# STM32Fx.net
KiCad netlist of a schematic drawn in Altium Designer
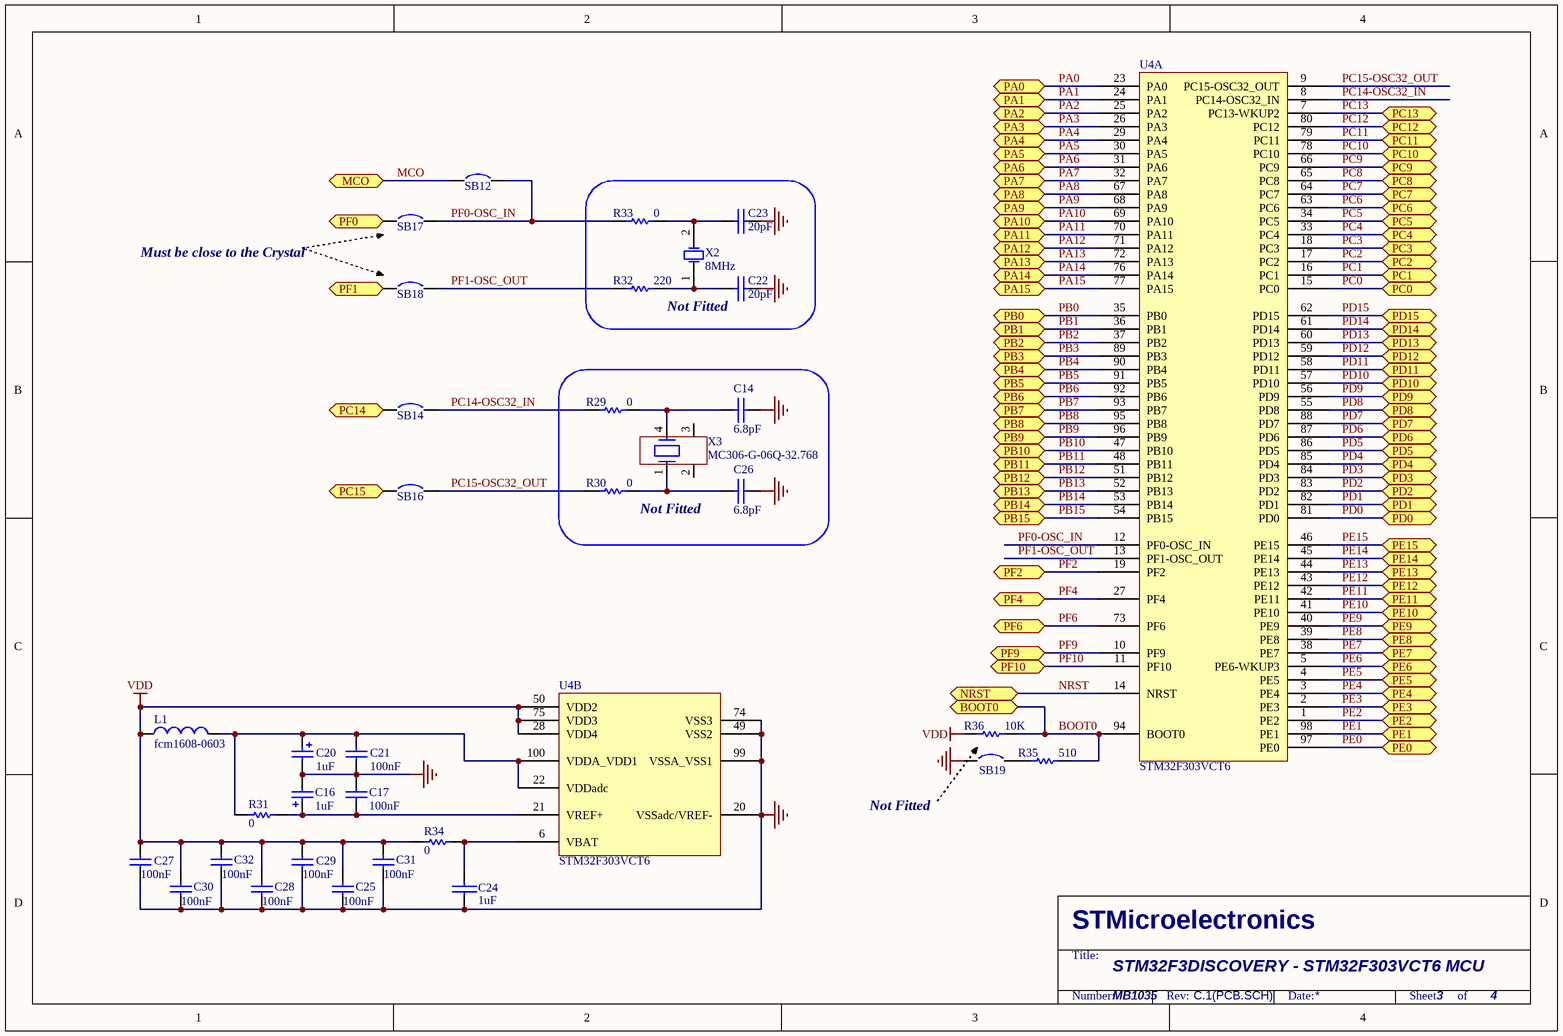
[diagram p0: STM32Fx.SchDoc]

(export (version "E")
  (design (tool "Eeschema 10.0.6"))
  (components
    (comp (ref "C14")
      (value "6.8pF")
      (footprint "0603C")
      (description "Capacitor")
      (libsource (lib "") (part "CAP_1"))
    )
    (comp (ref "C16")
      (value "1uF")
      (footprint "CASE-AA")
      (description "Polarized Capacitor (Radial)")
      (fields (field (name "PUBLISHER") "Altium Limited"))
      (libsource (lib "Miscellaneous Devices") (part "Cap Pol1"))
    )
    (comp (ref "C17")
      (value "100nF")
      (footprint "0603C")
      (description "Capacitor")
      (fields (field (name "PUBLISHER") "Altium Limited"))
      (libsource (lib "MB915_1") (part "Cap"))
    )
    (comp (ref "C20")
      (value "1uF")
      (footprint "CASE-AA")
      (description "Polarized Capacitor (Radial)")
      (fields (field (name "PUBLISHER") "Altium Limited"))
      (libsource (lib "Miscellaneous Devices") (part "Cap Pol1"))
    )
    (comp (ref "C21")
      (value "100nF")
      (footprint "0603C")
      (description "Capacitor")
      (fields (field (name "PUBLISHER") "Altium Limited"))
      (libsource (lib "MB915_1") (part "Cap"))
    )
    (comp (ref "C22")
      (value "20pF")
      (footprint "0603C")
      (description "Capacitor")
      (libsource (lib "*") (part "CAP"))
    )
    (comp (ref "C23")
      (value "20pF")
      (footprint "0603C")
      (description "Capacitor")
      (libsource (lib "*") (part "CAP"))
    )
    (comp (ref "C24")
      (value "1uF")
      (footprint "0603C")
      (description "Capacitor")
      (libsource (lib "*") (part "CAP"))
    )
    (comp (ref "C25")
      (value "100nF")
      (footprint "0603C")
      (description "Capacitor")
      (fields (field (name "PUBLISHER") "Altium Limited"))
      (libsource (lib "MB915_1") (part "Cap"))
    )
    (comp (ref "C26")
      (value "6.8pF")
      (footprint "0603C")
      (description "Capacitor")
      (libsource (lib "") (part "CAP_1"))
    )
    (comp (ref "C27")
      (value "100nF")
      (footprint "0603C")
      (description "Capacitor")
      (fields (field (name "PUBLISHER") "Altium Limited"))
      (libsource (lib "MB915_1") (part "Cap"))
    )
    (comp (ref "C28")
      (value "100nF")
      (footprint "0603C")
      (description "Capacitor")
      (fields (field (name "PUBLISHER") "Altium Limited"))
      (libsource (lib "MB915_1") (part "Cap"))
    )
    (comp (ref "C29")
      (value "100nF")
      (footprint "0603C")
      (description "Capacitor")
      (fields (field (name "PUBLISHER") "Altium Limited"))
      (libsource (lib "MB915_1") (part "Cap"))
    )
    (comp (ref "C30")
      (value "100nF")
      (footprint "0603C")
      (description "Capacitor")
      (fields (field (name "PUBLISHER") "Altium Limited"))
      (libsource (lib "MB915_1") (part "Cap"))
    )
    (comp (ref "C31")
      (value "100nF")
      (footprint "0603C")
      (description "Capacitor")
      (fields (field (name "PUBLISHER") "Altium Limited"))
      (libsource (lib "MB915_1") (part "Cap"))
    )
    (comp (ref "C32")
      (value "100nF")
      (footprint "0603C")
      (description "Capacitor")
      (fields (field (name "PUBLISHER") "Altium Limited"))
      (libsource (lib "MB915_1") (part "Cap"))
    )
    (comp (ref "L1")
      (value "fcm1608-0603")
      (footprint "0603L")
      (description "Inductor")
      (fields (field (name "PUBLISHER") "Altium Limited"))
      (libsource (lib "Miscellaneous Devices") (part "Inductor"))
    )
    (comp (ref "R29")
      (value "0")
      (footprint "0402R")
      (description "Resistor")
      (fields (field (name "PUBLISHER") "Altium Limited"))
      (libsource (lib "MB915_1") (part "res1"))
    )
    (comp (ref "R30")
      (value "0")
      (footprint "0402R")
      (description "Resistor")
      (fields (field (name "PUBLISHER") "Altium Limited"))
      (libsource (lib "MB915_1") (part "res1"))
    )
    (comp (ref "R31")
      (value "0")
      (footprint "0402R")
      (description "Resistor")
      (fields (field (name "PUBLISHER") "Altium Limited"))
      (libsource (lib "Miscellaneous Devices") (part "Res1"))
    )
    (comp (ref "R32")
      (value "220")
      (footprint "0402R")
      (description "Resistor")
      (fields (field (name "PUBLISHER") "Altium Limited"))
      (libsource (lib "MB915_1") (part "res1"))
    )
    (comp (ref "R33")
      (value "0")
      (footprint "0402R")
      (description "Resistor")
      (fields (field (name "PUBLISHER") "Altium Limited"))
      (libsource (lib "MB915_1") (part "res1"))
    )
    (comp (ref "R34")
      (value "0")
      (footprint "0402R")
      (description "Resistor")
      (fields (field (name "PUBLISHER") "Altium Limited"))
      (libsource (lib "Miscellaneous Devices") (part "Res1"))
    )
    (comp (ref "R35")
      (value "510")
      (footprint "0402R")
      (description "Resistor")
      (fields (field (name "PUBLISHER") "Altium Limited"))
      (libsource (lib "Miscellaneous Devices") (part "res1"))
    )
    (comp (ref "R36")
      (value "10K")
      (footprint "0402R")
      (description "Resistor")
      (fields (field (name "PUBLISHER") "Altium Limited"))
      (libsource (lib "Miscellaneous Devices") (part "res1"))
    )
    (comp (ref "SB12")
      (value "Circuit Breaker")
      (footprint "JP2_SMD")
      (fields (field (name "PUBLISHER") "Altium Limited"))
      (libsource (lib "MB915") (part "Circuit Breaker"))
    )
    (comp (ref "SB14")
      (value "Circuit Breaker")
      (footprint "JP2_SMD")
      (fields (field (name "PUBLISHER") "Altium Limited"))
      (libsource (lib "MB915") (part "Circuit Breaker"))
    )
    (comp (ref "SB16")
      (value "Circuit Breaker")
      (footprint "JP2_SMD")
      (fields (field (name "PUBLISHER") "Altium Limited"))
      (libsource (lib "MB915") (part "Circuit Breaker"))
    )
    (comp (ref "SB17")
      (value "Circuit Breaker")
      (footprint "JP2_SMD")
      (fields (field (name "PUBLISHER") "Altium Limited"))
      (libsource (lib "MB915") (part "Circuit Breaker"))
    )
    (comp (ref "SB18")
      (value "Circuit Breaker")
      (footprint "JP2_SMD")
      (fields (field (name "PUBLISHER") "Altium Limited"))
      (libsource (lib "MB915") (part "Circuit Breaker"))
    )
    (comp (ref "SB19")
      (value "Circuit Breaker")
      (footprint "JP2_SMD")
      (fields (field (name "PUBLISHER") "Altium Limited"))
      (libsource (lib "MB915") (part "Circuit Breaker"))
    )
    (comp (ref "U4")
      (value "STM32F303VCT6")
      (footprint "LQFP100")
      (description "STM32F303VCT6 (Manta-Edge)")
      (libsource (lib "MCD_TOOLS") (part "STM32F303VCT6"))
    )
    (comp (ref "X2")
      (value "8MHz")
      (footprint "XTAL1")
      (description "Crystal Oscillator")
      (fields (field (name "PUBLISHER") "Altium Limited"))
      (libsource (lib "MB963_1") (part "XTAL"))
    )
    (comp (ref "X3")
      (value "MC306-G-06Q-32.768")
      (footprint "MC306-CRYSTAL")
      (libsource (lib "*") (part "MC306"))
    )
  )
  (nets
    (net (code "1") (name "/BOOT0") (class "Default")
      (node (ref "R35") (pin "2") (pinfunction "2_2") (pintype "passive"))
      (node (ref "R36") (pin "2") (pinfunction "2_2") (pintype "passive"))
      (node (ref "U4") (pin "94") (pinfunction "BOOT0_94") (pintype "passive"))
    )
    (net (code "2") (name "/MCO") (class "Default")
      (node (ref "SB12") (pin "1") (pinfunction "1_1") (pintype "passive"))
    )
    (net (code "3") (name "/NRST") (class "Default")
      (node (ref "U4") (pin "14") (pinfunction "NRST_14") (pintype "passive"))
    )
    (net (code "4") (name "/PA0") (class "Default")
      (node (ref "U4") (pin "23") (pinfunction "PA0_23") (pintype "passive"))
    )
    (net (code "5") (name "/PA1") (class "Default")
      (node (ref "U4") (pin "24") (pinfunction "PA1_24") (pintype "passive"))
    )
    (net (code "6") (name "/PA2") (class "Default")
      (node (ref "U4") (pin "25") (pinfunction "PA2_25") (pintype "passive"))
    )
    (net (code "7") (name "/PA3") (class "Default")
      (node (ref "U4") (pin "26") (pinfunction "PA3_26") (pintype "passive"))
    )
    (net (code "8") (name "/PA4") (class "Default")
      (node (ref "U4") (pin "29") (pinfunction "PA4_29") (pintype "passive"))
    )
    (net (code "9") (name "/PA5") (class "Default")
      (node (ref "U4") (pin "30") (pinfunction "PA5_30") (pintype "passive"))
    )
    (net (code "10") (name "/PA6") (class "Default")
      (node (ref "U4") (pin "31") (pinfunction "PA6_31") (pintype "passive"))
    )
    (net (code "11") (name "/PA7") (class "Default")
      (node (ref "U4") (pin "32") (pinfunction "PA7_32") (pintype "passive"))
    )
    (net (code "12") (name "/PA8") (class "Default")
      (node (ref "U4") (pin "67") (pinfunction "PA8_67") (pintype "passive"))
    )
    (net (code "13") (name "/PA9") (class "Default")
      (node (ref "U4") (pin "68") (pinfunction "PA9_68") (pintype "passive"))
    )
    (net (code "14") (name "/PA10") (class "Default")
      (node (ref "U4") (pin "69") (pinfunction "PA10_69") (pintype "passive"))
    )
    (net (code "15") (name "/PA11") (class "Default")
      (node (ref "U4") (pin "70") (pinfunction "PA11_70") (pintype "passive"))
    )
    (net (code "16") (name "/PA12") (class "Default")
      (node (ref "U4") (pin "71") (pinfunction "PA12_71") (pintype "passive"))
    )
    (net (code "17") (name "/PA13") (class "Default")
      (node (ref "U4") (pin "72") (pinfunction "PA13_72") (pintype "passive"))
    )
    (net (code "18") (name "/PA14") (class "Default")
      (node (ref "U4") (pin "76") (pinfunction "PA14_76") (pintype "passive"))
    )
    (net (code "19") (name "/PA15") (class "Default")
      (node (ref "U4") (pin "77") (pinfunction "PA15_77") (pintype "passive"))
    )
    (net (code "20") (name "/PB0") (class "Default")
      (node (ref "U4") (pin "35") (pinfunction "PB0_35") (pintype "passive"))
    )
    (net (code "21") (name "/PB1") (class "Default")
      (node (ref "U4") (pin "36") (pinfunction "PB1_36") (pintype "passive"))
    )
    (net (code "22") (name "/PB2") (class "Default")
      (node (ref "U4") (pin "37") (pinfunction "PB2_37") (pintype "passive"))
    )
    (net (code "23") (name "/PB3") (class "Default")
      (node (ref "U4") (pin "89") (pinfunction "PB3_89") (pintype "passive"))
    )
    (net (code "24") (name "/PB4") (class "Default")
      (node (ref "U4") (pin "90") (pinfunction "PB4_90") (pintype "passive"))
    )
    (net (code "25") (name "/PB5") (class "Default")
      (node (ref "U4") (pin "91") (pinfunction "PB5_91") (pintype "passive"))
    )
    (net (code "26") (name "/PB6") (class "Default")
      (node (ref "U4") (pin "92") (pinfunction "PB6_92") (pintype "passive"))
    )
    (net (code "27") (name "/PB7") (class "Default")
      (node (ref "U4") (pin "93") (pinfunction "PB7_93") (pintype "passive"))
    )
    (net (code "28") (name "/PB8") (class "Default")
      (node (ref "U4") (pin "95") (pinfunction "PB8_95") (pintype "passive"))
    )
    (net (code "29") (name "/PB9") (class "Default")
      (node (ref "U4") (pin "96") (pinfunction "PB9_96") (pintype "passive"))
    )
    (net (code "30") (name "/PB10") (class "Default")
      (node (ref "U4") (pin "47") (pinfunction "PB10_47") (pintype "passive"))
    )
    (net (code "31") (name "/PB11") (class "Default")
      (node (ref "U4") (pin "48") (pinfunction "PB11_48") (pintype "passive"))
    )
    (net (code "32") (name "/PB12") (class "Default")
      (node (ref "U4") (pin "51") (pinfunction "PB12_51") (pintype "passive"))
    )
    (net (code "33") (name "/PB13") (class "Default")
      (node (ref "U4") (pin "52") (pinfunction "PB13_52") (pintype "passive"))
    )
    (net (code "34") (name "/PB14") (class "Default")
      (node (ref "U4") (pin "53") (pinfunction "PB14_53") (pintype "passive"))
    )
    (net (code "35") (name "/PB15") (class "Default")
      (node (ref "U4") (pin "54") (pinfunction "PB15_54") (pintype "passive"))
    )
    (net (code "36") (name "/PC0") (class "Default")
      (node (ref "U4") (pin "15") (pinfunction "PC0_15") (pintype "passive"))
    )
    (net (code "37") (name "/PC1") (class "Default")
      (node (ref "U4") (pin "16") (pinfunction "PC1_16") (pintype "passive"))
    )
    (net (code "38") (name "/PC2") (class "Default")
      (node (ref "U4") (pin "17") (pinfunction "PC2_17") (pintype "passive"))
    )
    (net (code "39") (name "/PC3") (class "Default")
      (node (ref "U4") (pin "18") (pinfunction "PC3_18") (pintype "passive"))
    )
    (net (code "40") (name "/PC4") (class "Default")
      (node (ref "U4") (pin "33") (pinfunction "PC4_33") (pintype "passive"))
    )
    (net (code "41") (name "/PC5") (class "Default")
      (node (ref "U4") (pin "34") (pinfunction "PC5_34") (pintype "passive"))
    )
    (net (code "42") (name "/PC6") (class "Default")
      (node (ref "U4") (pin "63") (pinfunction "PC6_63") (pintype "passive"))
    )
    (net (code "43") (name "/PC7") (class "Default")
      (node (ref "U4") (pin "64") (pinfunction "PC7_64") (pintype "passive"))
    )
    (net (code "44") (name "/PC8") (class "Default")
      (node (ref "U4") (pin "65") (pinfunction "PC8_65") (pintype "passive"))
    )
    (net (code "45") (name "/PC9") (class "Default")
      (node (ref "U4") (pin "66") (pinfunction "PC9_66") (pintype "passive"))
    )
    (net (code "46") (name "/PC10") (class "Default")
      (node (ref "U4") (pin "78") (pinfunction "PC10_78") (pintype "passive"))
    )
    (net (code "47") (name "/PC11") (class "Default")
      (node (ref "U4") (pin "79") (pinfunction "PC11_79") (pintype "passive"))
    )
    (net (code "48") (name "/PC12") (class "Default")
      (node (ref "U4") (pin "80") (pinfunction "PC12_80") (pintype "passive"))
    )
    (net (code "49") (name "/PC13") (class "Default")
      (node (ref "U4") (pin "7") (pinfunction "PC13-WKUP2_7") (pintype "passive"))
    )
    (net (code "50") (name "/PC14") (class "Default")
      (node (ref "SB14") (pin "1") (pinfunction "1_1") (pintype "passive"))
    )
    (net (code "51") (name "/PC14-OSC32_IN") (class "Default")
      (node (ref "R29") (pin "1") (pinfunction "1_1") (pintype "passive"))
      (node (ref "SB14") (pin "2") (pinfunction "2_2") (pintype "passive"))
      (node (ref "U4") (pin "8") (pinfunction "PC14-OSC32_IN_8") (pintype "passive"))
    )
    (net (code "52") (name "/PC15") (class "Default")
      (node (ref "SB16") (pin "1") (pinfunction "1_1") (pintype "passive"))
    )
    (net (code "53") (name "/PC15-OSC32_OUT") (class "Default")
      (node (ref "R30") (pin "1") (pinfunction "1_1") (pintype "passive"))
      (node (ref "SB16") (pin "2") (pinfunction "2_2") (pintype "passive"))
      (node (ref "U4") (pin "9") (pinfunction "PC15-OSC32_OUT_9") (pintype "passive"))
    )
    (net (code "54") (name "/PD0") (class "Default")
      (node (ref "U4") (pin "81") (pinfunction "PD0_81") (pintype "passive"))
    )
    (net (code "55") (name "/PD1") (class "Default")
      (node (ref "U4") (pin "82") (pinfunction "PD1_82") (pintype "passive"))
    )
    (net (code "56") (name "/PD2") (class "Default")
      (node (ref "U4") (pin "83") (pinfunction "PD2_83") (pintype "passive"))
    )
    (net (code "57") (name "/PD3") (class "Default")
      (node (ref "U4") (pin "84") (pinfunction "PD3_84") (pintype "passive"))
    )
    (net (code "58") (name "/PD4") (class "Default")
      (node (ref "U4") (pin "85") (pinfunction "PD4_85") (pintype "passive"))
    )
    (net (code "59") (name "/PD5") (class "Default")
      (node (ref "U4") (pin "86") (pinfunction "PD5_86") (pintype "passive"))
    )
    (net (code "60") (name "/PD6") (class "Default")
      (node (ref "U4") (pin "87") (pinfunction "PD6_87") (pintype "passive"))
    )
    (net (code "61") (name "/PD7") (class "Default")
      (node (ref "U4") (pin "88") (pinfunction "PD7_88") (pintype "passive"))
    )
    (net (code "62") (name "/PD8") (class "Default")
      (node (ref "U4") (pin "55") (pinfunction "PD8_55") (pintype "passive"))
    )
    (net (code "63") (name "/PD9") (class "Default")
      (node (ref "U4") (pin "56") (pinfunction "PD9_56") (pintype "passive"))
    )
    (net (code "64") (name "/PD10") (class "Default")
      (node (ref "U4") (pin "57") (pinfunction "PD10_57") (pintype "passive"))
    )
    (net (code "65") (name "/PD11") (class "Default")
      (node (ref "U4") (pin "58") (pinfunction "PD11_58") (pintype "passive"))
    )
    (net (code "66") (name "/PD12") (class "Default")
      (node (ref "U4") (pin "59") (pinfunction "PD12_59") (pintype "passive"))
    )
    (net (code "67") (name "/PD13") (class "Default")
      (node (ref "U4") (pin "60") (pinfunction "PD13_60") (pintype "passive"))
    )
    (net (code "68") (name "/PD14") (class "Default")
      (node (ref "U4") (pin "61") (pinfunction "PD14_61") (pintype "passive"))
    )
    (net (code "69") (name "/PD15") (class "Default")
      (node (ref "U4") (pin "62") (pinfunction "PD15_62") (pintype "passive"))
    )
    (net (code "70") (name "/PE0") (class "Default")
      (node (ref "U4") (pin "97") (pinfunction "PE0_97") (pintype "passive"))
    )
    (net (code "71") (name "/PE1") (class "Default")
      (node (ref "U4") (pin "98") (pinfunction "PE1_98") (pintype "passive"))
    )
    (net (code "72") (name "/PE2") (class "Default")
      (node (ref "U4") (pin "1") (pinfunction "PE2_1") (pintype "passive"))
    )
    (net (code "73") (name "/PE3") (class "Default")
      (node (ref "U4") (pin "2") (pinfunction "PE3_2") (pintype "passive"))
    )
    (net (code "74") (name "/PE4") (class "Default")
      (node (ref "U4") (pin "3") (pinfunction "PE4_3") (pintype "passive"))
    )
    (net (code "75") (name "/PE5") (class "Default")
      (node (ref "U4") (pin "4") (pinfunction "PE5_4") (pintype "passive"))
    )
    (net (code "76") (name "/PE6") (class "Default")
      (node (ref "U4") (pin "5") (pinfunction "PE6-WKUP3_5") (pintype "passive"))
    )
    (net (code "77") (name "/PE7") (class "Default")
      (node (ref "U4") (pin "38") (pinfunction "PE7_38") (pintype "passive"))
    )
    (net (code "78") (name "/PE8") (class "Default")
      (node (ref "U4") (pin "39") (pinfunction "PE8_39") (pintype "passive"))
    )
    (net (code "79") (name "/PE9") (class "Default")
      (node (ref "U4") (pin "40") (pinfunction "PE9_40") (pintype "passive"))
    )
    (net (code "80") (name "/PE10") (class "Default")
      (node (ref "U4") (pin "41") (pinfunction "PE10_41") (pintype "passive"))
    )
    (net (code "81") (name "/PE11") (class "Default")
      (node (ref "U4") (pin "42") (pinfunction "PE11_42") (pintype "passive"))
    )
    (net (code "82") (name "/PE12") (class "Default")
      (node (ref "U4") (pin "43") (pinfunction "PE12_43") (pintype "passive"))
    )
    (net (code "83") (name "/PE13") (class "Default")
      (node (ref "U4") (pin "44") (pinfunction "PE13_44") (pintype "passive"))
    )
    (net (code "84") (name "/PE14") (class "Default")
      (node (ref "U4") (pin "45") (pinfunction "PE14_45") (pintype "passive"))
    )
    (net (code "85") (name "/PE15") (class "Default")
      (node (ref "U4") (pin "46") (pinfunction "PE15_46") (pintype "passive"))
    )
    (net (code "86") (name "/PF0") (class "Default")
      (node (ref "SB17") (pin "1") (pinfunction "1_1") (pintype "passive"))
    )
    (net (code "87") (name "/PF0-OSC_IN") (class "Default")
      (node (ref "R33") (pin "1") (pinfunction "1_1") (pintype "passive"))
      (node (ref "SB12") (pin "2") (pinfunction "2_2") (pintype "passive"))
      (node (ref "SB17") (pin "2") (pinfunction "2_2") (pintype "passive"))
      (node (ref "U4") (pin "12") (pinfunction "PF0-OSC_IN_12") (pintype "passive"))
    )
    (net (code "88") (name "/PF1") (class "Default")
      (node (ref "SB18") (pin "1") (pinfunction "1_1") (pintype "passive"))
    )
    (net (code "89") (name "/PF1-OSC_OUT") (class "Default")
      (node (ref "R32") (pin "1") (pinfunction "1_1") (pintype "passive"))
      (node (ref "SB18") (pin "2") (pinfunction "2_2") (pintype "passive"))
      (node (ref "U4") (pin "13") (pinfunction "PF1-OSC_OUT_13") (pintype "passive"))
    )
    (net (code "90") (name "/PF2") (class "Default")
      (node (ref "U4") (pin "19") (pinfunction "PF2_19") (pintype "passive"))
    )
    (net (code "91") (name "/PF4") (class "Default")
      (node (ref "U4") (pin "27") (pinfunction "PF4_27") (pintype "passive"))
    )
    (net (code "92") (name "/PF6") (class "Default")
      (node (ref "U4") (pin "73") (pinfunction "PF6_73") (pintype "passive"))
    )
    (net (code "93") (name "/PF9") (class "Default")
      (node (ref "U4") (pin "10") (pinfunction "PF9_10") (pintype "passive"))
    )
    (net (code "94") (name "/PF10") (class "Default")
      (node (ref "U4") (pin "11") (pinfunction "PF10_11") (pintype "passive"))
    )
    (net (code "95") (name "GND") (class "Default")
      (node (ref "C14") (pin "2") (pinfunction "2_2") (pintype "passive"))
      (node (ref "C16") (pin "2") (pinfunction "2_2") (pintype "passive"))
      (node (ref "C17") (pin "1") (pinfunction "1_1") (pintype "passive"))
      (node (ref "C20") (pin "2") (pinfunction "2_2") (pintype "passive"))
      (node (ref "C21") (pin "1") (pinfunction "1_1") (pintype "passive"))
      (node (ref "C22") (pin "1") (pinfunction "1_1") (pintype "passive"))
      (node (ref "C23") (pin "1") (pinfunction "1_1") (pintype "passive"))
      (node (ref "C24") (pin "2") (pinfunction "2_2") (pintype "passive"))
      (node (ref "C25") (pin "1") (pinfunction "1_1") (pintype "passive"))
      (node (ref "C26") (pin "2") (pinfunction "2_2") (pintype "passive"))
      (node (ref "C27") (pin "1") (pinfunction "1_1") (pintype "passive"))
      (node (ref "C28") (pin "1") (pinfunction "1_1") (pintype "passive"))
      (node (ref "C29") (pin "1") (pinfunction "1_1") (pintype "passive"))
      (node (ref "C30") (pin "1") (pinfunction "1_1") (pintype "passive"))
      (node (ref "C31") (pin "2") (pinfunction "2_2") (pintype "passive"))
      (node (ref "C32") (pin "2") (pinfunction "2_2") (pintype "passive"))
      (node (ref "SB19") (pin "1") (pinfunction "1_1") (pintype "passive"))
      (node (ref "U4") (pin "20") (pinfunction "VSSadc/VREF-_20") (pintype "passive"))
      (node (ref "U4") (pin "49") (pinfunction "VSS2_49") (pintype "passive"))
      (node (ref "U4") (pin "74") (pinfunction "VSS3_74") (pintype "passive"))
      (node (ref "U4") (pin "99") (pinfunction "VSSA_VSS1_99") (pintype "passive"))
    )
    (net (code "96") (name "Net-(C14-Pad1)") (class "Default")
      (node (ref "C14") (pin "1") (pinfunction "1_1") (pintype "passive"))
      (node (ref "R29") (pin "2") (pinfunction "2_2") (pintype "passive"))
      (node (ref "X3") (pin "4") (pinfunction "4_4") (pintype "passive"))
    )
    (net (code "97") (name "Net-(C26-Pad1)") (class "Default")
      (node (ref "C26") (pin "1") (pinfunction "1_1") (pintype "passive"))
      (node (ref "R30") (pin "2") (pinfunction "2_2") (pintype "passive"))
      (node (ref "X3") (pin "1") (pinfunction "1_1") (pintype "passive"))
    )
    (net (code "98") (name "Net-(R35-Pad1)") (class "Default")
      (node (ref "R35") (pin "1") (pinfunction "1_1") (pintype "passive"))
      (node (ref "SB19") (pin "2") (pinfunction "2_2") (pintype "passive"))
    )
    (net (code "99") (name "Net-(U4B-VBAT)") (class "Default")
      (node (ref "C24") (pin "1") (pinfunction "1_1") (pintype "passive"))
      (node (ref "R34") (pin "1") (pinfunction "1_1") (pintype "passive"))
      (node (ref "U4") (pin "6") (pinfunction "VBAT_6") (pintype "passive"))
    )
    (net (code "100") (name "Net-(U4B-VDDA_VDD1)") (class "Default")
      (node (ref "C20") (pin "1") (pinfunction "1_1") (pintype "passive"))
      (node (ref "C21") (pin "2") (pinfunction "2_2") (pintype "passive"))
      (node (ref "L1") (pin "2") (pinfunction "2_2") (pintype "passive"))
      (node (ref "R31") (pin "2") (pinfunction "2_2") (pintype "passive"))
      (node (ref "U4") (pin "100") (pinfunction "VDDA_VDD1_100") (pintype "passive"))
      (node (ref "U4") (pin "22") (pinfunction "VDDadc_22") (pintype "passive"))
    )
    (net (code "101") (name "Net-(U4B-VREF+)") (class "Default")
      (node (ref "C16") (pin "1") (pinfunction "1_1") (pintype "passive"))
      (node (ref "C17") (pin "2") (pinfunction "2_2") (pintype "passive"))
      (node (ref "R31") (pin "1") (pinfunction "1_1") (pintype "passive"))
      (node (ref "U4") (pin "21") (pinfunction "VREF+_21") (pintype "passive"))
    )
    (net (code "102") (name "Net-(X2-OSC1)") (class "Default")
      (node (ref "C22") (pin "2") (pinfunction "2_2") (pintype "passive"))
      (node (ref "R32") (pin "2") (pinfunction "2_2") (pintype "passive"))
      (node (ref "X2") (pin "1") (pinfunction "OSC1_1") (pintype "passive"))
    )
    (net (code "103") (name "Net-(X2-OSC2)") (class "Default")
      (node (ref "C23") (pin "2") (pinfunction "2_2") (pintype "passive"))
      (node (ref "R33") (pin "2") (pinfunction "2_2") (pintype "passive"))
      (node (ref "X2") (pin "2") (pinfunction "OSC2_2") (pintype "passive"))
    )
    (net (code "104") (name "VDD") (class "Default")
      (node (ref "C25") (pin "2") (pinfunction "2_2") (pintype "passive"))
      (node (ref "C27") (pin "2") (pinfunction "2_2") (pintype "passive"))
      (node (ref "C28") (pin "2") (pinfunction "2_2") (pintype "passive"))
      (node (ref "C29") (pin "2") (pinfunction "2_2") (pintype "passive"))
      (node (ref "C30") (pin "2") (pinfunction "2_2") (pintype "passive"))
      (node (ref "C31") (pin "1") (pinfunction "1_1") (pintype "passive"))
      (node (ref "C32") (pin "1") (pinfunction "1_1") (pintype "passive"))
      (node (ref "L1") (pin "1") (pinfunction "1_1") (pintype "passive"))
      (node (ref "R34") (pin "2") (pinfunction "2_2") (pintype "passive"))
      (node (ref "R36") (pin "1") (pinfunction "1_1") (pintype "passive"))
      (node (ref "U4") (pin "28") (pinfunction "VDD4_28") (pintype "passive"))
      (node (ref "U4") (pin "50") (pinfunction "VDD2_50") (pintype "passive"))
      (node (ref "U4") (pin "75") (pinfunction "VDD3_75") (pintype "passive"))
    )
    (net (code "105") (name "unconnected-(X3-Pad2)") (class "Default")
      (node (ref "X3") (pin "2") (pinfunction "2_2") (pintype "passive"))
    )
    (net (code "106") (name "unconnected-(X3-Pad3)") (class "Default")
      (node (ref "X3") (pin "3") (pinfunction "3_3") (pintype "passive"))
    )
  )
)
